# Nusbio1_0_WaveShare_WithLed_SeedStudio.net
KiCad netlist of a schematic drawn in EAGLE
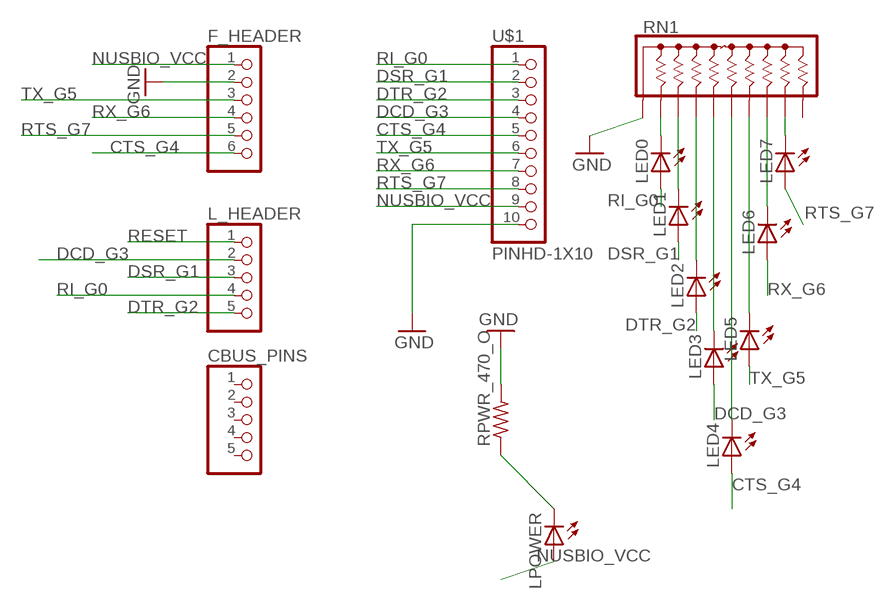
[diagram p0: schematic, sheet 1]

(export (version "E")
  (design (tool "Eeschema 10.0.6"))
  (components
    (comp (ref "CBUS_PINS")
      (value "PINHD-1X5")
      (footprint "eagle-import:1X05")
      (libsource (lib "eagle-import") (part "PINHD-1X5"))
    )
    (comp (ref "F_HEADER")
      (value "PINHD-1X6")
      (footprint "eagle-import:1X06")
      (libsource (lib "eagle-import") (part "PINHD-1X6"))
    )
    (comp (ref "LED0")
      (value "LEDSMT1206")
      (footprint "eagle-import:1206")
      (libsource (lib "eagle-import") (part "LEDSMT1206"))
    )
    (comp (ref "LED1")
      (value "LEDSMT1206")
      (footprint "eagle-import:1206")
      (libsource (lib "eagle-import") (part "LEDSMT1206"))
    )
    (comp (ref "LED2")
      (value "LEDSMT1206")
      (footprint "eagle-import:1206")
      (libsource (lib "eagle-import") (part "LEDSMT1206"))
    )
    (comp (ref "LED3")
      (value "LEDSMT1206")
      (footprint "eagle-import:1206")
      (libsource (lib "eagle-import") (part "LEDSMT1206"))
    )
    (comp (ref "LED4")
      (value "LEDSMT1206")
      (footprint "eagle-import:1206")
      (libsource (lib "eagle-import") (part "LEDSMT1206"))
    )
    (comp (ref "LED5")
      (value "LEDSMT1206")
      (footprint "eagle-import:1206")
      (libsource (lib "eagle-import") (part "LEDSMT1206"))
    )
    (comp (ref "LED6")
      (value "LEDSMT1206")
      (footprint "eagle-import:1206")
      (libsource (lib "eagle-import") (part "LEDSMT1206"))
    )
    (comp (ref "LED7")
      (value "LEDSMT1206")
      (footprint "eagle-import:1206")
      (libsource (lib "eagle-import") (part "LEDSMT1206"))
    )
    (comp (ref "LPOWER")
      (value "LEDSMT1206")
      (footprint "eagle-import:1206")
      (libsource (lib "eagle-import") (part "LEDSMT1206"))
    )
    (comp (ref "L_HEADER")
      (value "PINHD-1X5")
      (footprint "eagle-import:1X05")
      (libsource (lib "eagle-import") (part "PINHD-1X5"))
    )
    (comp (ref "RN1")
      (value "4610X")
      (footprint "eagle-import:SIP10")
      (libsource (lib "eagle-import") (part "4610X"))
    )
    (comp (ref "RPWR_470_O")
      (value "R-US_R1206")
      (footprint "eagle-import:R1206")
      (libsource (lib "eagle-import") (part "R-US_R1206"))
    )
    (comp (ref "U$1")
      (value "PINHD-1X10")
      (footprint "eagle-import:1X10-BIG")
      (libsource (lib "eagle-import") (part "PINHD-1X10"))
    )
  )
  (nets
    (net (code "1") (name "/CTS_G4") (class "Default")
      (node (ref "F_HEADER") (pin "6") (pinfunction "6_6") (pintype "passive"))
      (node (ref "LED4") (pin "A") (pinfunction "A_A") (pintype "passive"))
      (node (ref "U$1") (pin "5") (pinfunction "5_5") (pintype "passive"))
    )
    (net (code "2") (name "/DCD_G3") (class "Default")
      (node (ref "LED3") (pin "A") (pinfunction "A_A") (pintype "passive"))
      (node (ref "L_HEADER") (pin "2") (pinfunction "2_2") (pintype "passive"))
      (node (ref "U$1") (pin "4") (pinfunction "4_4") (pintype "passive"))
    )
    (net (code "3") (name "/DSR_G1") (class "Default")
      (node (ref "LED1") (pin "A") (pinfunction "A_A") (pintype "passive"))
      (node (ref "L_HEADER") (pin "3") (pinfunction "3_3") (pintype "passive"))
      (node (ref "U$1") (pin "2") (pinfunction "2_2") (pintype "passive"))
    )
    (net (code "4") (name "/DTR_G2") (class "Default")
      (node (ref "LED2") (pin "A") (pinfunction "A_A") (pintype "passive"))
      (node (ref "L_HEADER") (pin "5") (pinfunction "5_5") (pintype "passive"))
      (node (ref "U$1") (pin "3") (pinfunction "3_3") (pintype "passive"))
    )
    (net (code "5") (name "/NUSBIO_VCC") (class "Default")
      (node (ref "F_HEADER") (pin "1") (pinfunction "1_1") (pintype "passive"))
      (node (ref "LPOWER") (pin "A") (pinfunction "A_A") (pintype "passive"))
      (node (ref "U$1") (pin "9") (pinfunction "9_9") (pintype "passive"))
    )
    (net (code "6") (name "/RESET") (class "Default")
      (node (ref "L_HEADER") (pin "1") (pinfunction "1_1") (pintype "passive"))
    )
    (net (code "7") (name "/RI_G0") (class "Default")
      (node (ref "LED0") (pin "A") (pinfunction "A_A") (pintype "passive"))
      (node (ref "L_HEADER") (pin "4") (pinfunction "4_4") (pintype "passive"))
      (node (ref "U$1") (pin "1") (pinfunction "1_1") (pintype "passive"))
    )
    (net (code "8") (name "/RTS_G7") (class "Default")
      (node (ref "F_HEADER") (pin "5") (pinfunction "5_5") (pintype "passive"))
      (node (ref "LED7") (pin "A") (pinfunction "A_A") (pintype "passive"))
      (node (ref "U$1") (pin "8") (pinfunction "8_8") (pintype "passive"))
    )
    (net (code "9") (name "/RX_G6") (class "Default")
      (node (ref "F_HEADER") (pin "4") (pinfunction "4_4") (pintype "passive"))
      (node (ref "LED6") (pin "A") (pinfunction "A_A") (pintype "passive"))
      (node (ref "U$1") (pin "7") (pinfunction "7_7") (pintype "passive"))
    )
    (net (code "10") (name "/TX_G5") (class "Default")
      (node (ref "F_HEADER") (pin "3") (pinfunction "3_3") (pintype "passive"))
      (node (ref "LED5") (pin "A") (pinfunction "A_A") (pintype "passive"))
      (node (ref "U$1") (pin "6") (pinfunction "6_6") (pintype "passive"))
    )
    (net (code "11") (name "GND") (class "Default")
      (node (ref "F_HEADER") (pin "2") (pinfunction "2_2") (pintype "passive"))
      (node (ref "RN1") (pin "1") (pinfunction "1_1") (pintype "passive"))
      (node (ref "RPWR_470_O") (pin "2") (pinfunction "2_2") (pintype "passive"))
      (node (ref "U$1") (pin "10") (pinfunction "10_10") (pintype "passive"))
    )
    (net (code "12") (name "Net-(LED0-PadC)") (class "Default")
      (node (ref "LED0") (pin "C") (pinfunction "C_C") (pintype "passive"))
      (node (ref "RN1") (pin "2") (pinfunction "2_2") (pintype "passive"))
    )
    (net (code "13") (name "Net-(LED1-PadC)") (class "Default")
      (node (ref "LED1") (pin "C") (pinfunction "C_C") (pintype "passive"))
      (node (ref "RN1") (pin "3") (pinfunction "3_3") (pintype "passive"))
    )
    (net (code "14") (name "Net-(LED2-PadC)") (class "Default")
      (node (ref "LED2") (pin "C") (pinfunction "C_C") (pintype "passive"))
      (node (ref "RN1") (pin "4") (pinfunction "4_4") (pintype "passive"))
    )
    (net (code "15") (name "Net-(LED3-PadC)") (class "Default")
      (node (ref "LED3") (pin "C") (pinfunction "C_C") (pintype "passive"))
      (node (ref "RN1") (pin "5") (pinfunction "5_5") (pintype "passive"))
    )
    (net (code "16") (name "Net-(LED4-PadC)") (class "Default")
      (node (ref "LED4") (pin "C") (pinfunction "C_C") (pintype "passive"))
      (node (ref "RN1") (pin "6") (pinfunction "6_6") (pintype "passive"))
    )
    (net (code "17") (name "Net-(LED5-PadC)") (class "Default")
      (node (ref "LED5") (pin "C") (pinfunction "C_C") (pintype "passive"))
      (node (ref "RN1") (pin "7") (pinfunction "7_7") (pintype "passive"))
    )
    (net (code "18") (name "Net-(LED6-PadC)") (class "Default")
      (node (ref "LED6") (pin "C") (pinfunction "C_C") (pintype "passive"))
      (node (ref "RN1") (pin "8") (pinfunction "8_8") (pintype "passive"))
    )
    (net (code "19") (name "Net-(LED7-PadC)") (class "Default")
      (node (ref "LED7") (pin "C") (pinfunction "C_C") (pintype "passive"))
      (node (ref "RN1") (pin "9") (pinfunction "9_9") (pintype "passive"))
    )
    (net (code "20") (name "Net-(LPOWER-PadC)") (class "Default")
      (node (ref "LPOWER") (pin "C") (pinfunction "C_C") (pintype "passive"))
      (node (ref "RPWR_470_O") (pin "1") (pinfunction "1_1") (pintype "passive"))
    )
    (net (code "21") (name "unconnected-(CBUS_PINS-Pad1)") (class "Default")
      (node (ref "CBUS_PINS") (pin "1") (pinfunction "1_1") (pintype "passive"))
    )
    (net (code "22") (name "unconnected-(CBUS_PINS-Pad2)") (class "Default")
      (node (ref "CBUS_PINS") (pin "2") (pinfunction "2_2") (pintype "passive"))
    )
    (net (code "23") (name "unconnected-(CBUS_PINS-Pad3)") (class "Default")
      (node (ref "CBUS_PINS") (pin "3") (pinfunction "3_3") (pintype "passive"))
    )
    (net (code "24") (name "unconnected-(CBUS_PINS-Pad4)") (class "Default")
      (node (ref "CBUS_PINS") (pin "4") (pinfunction "4_4") (pintype "passive"))
    )
    (net (code "25") (name "unconnected-(CBUS_PINS-Pad5)") (class "Default")
      (node (ref "CBUS_PINS") (pin "5") (pinfunction "5_5") (pintype "passive"))
    )
    (net (code "26") (name "unconnected-(RN1-Pad10)") (class "Default")
      (node (ref "RN1") (pin "10") (pinfunction "10_10") (pintype "passive"))
    )
  )
)
